# r0_2_6.net
KiCad netlist of a schematic drawn in EAGLE
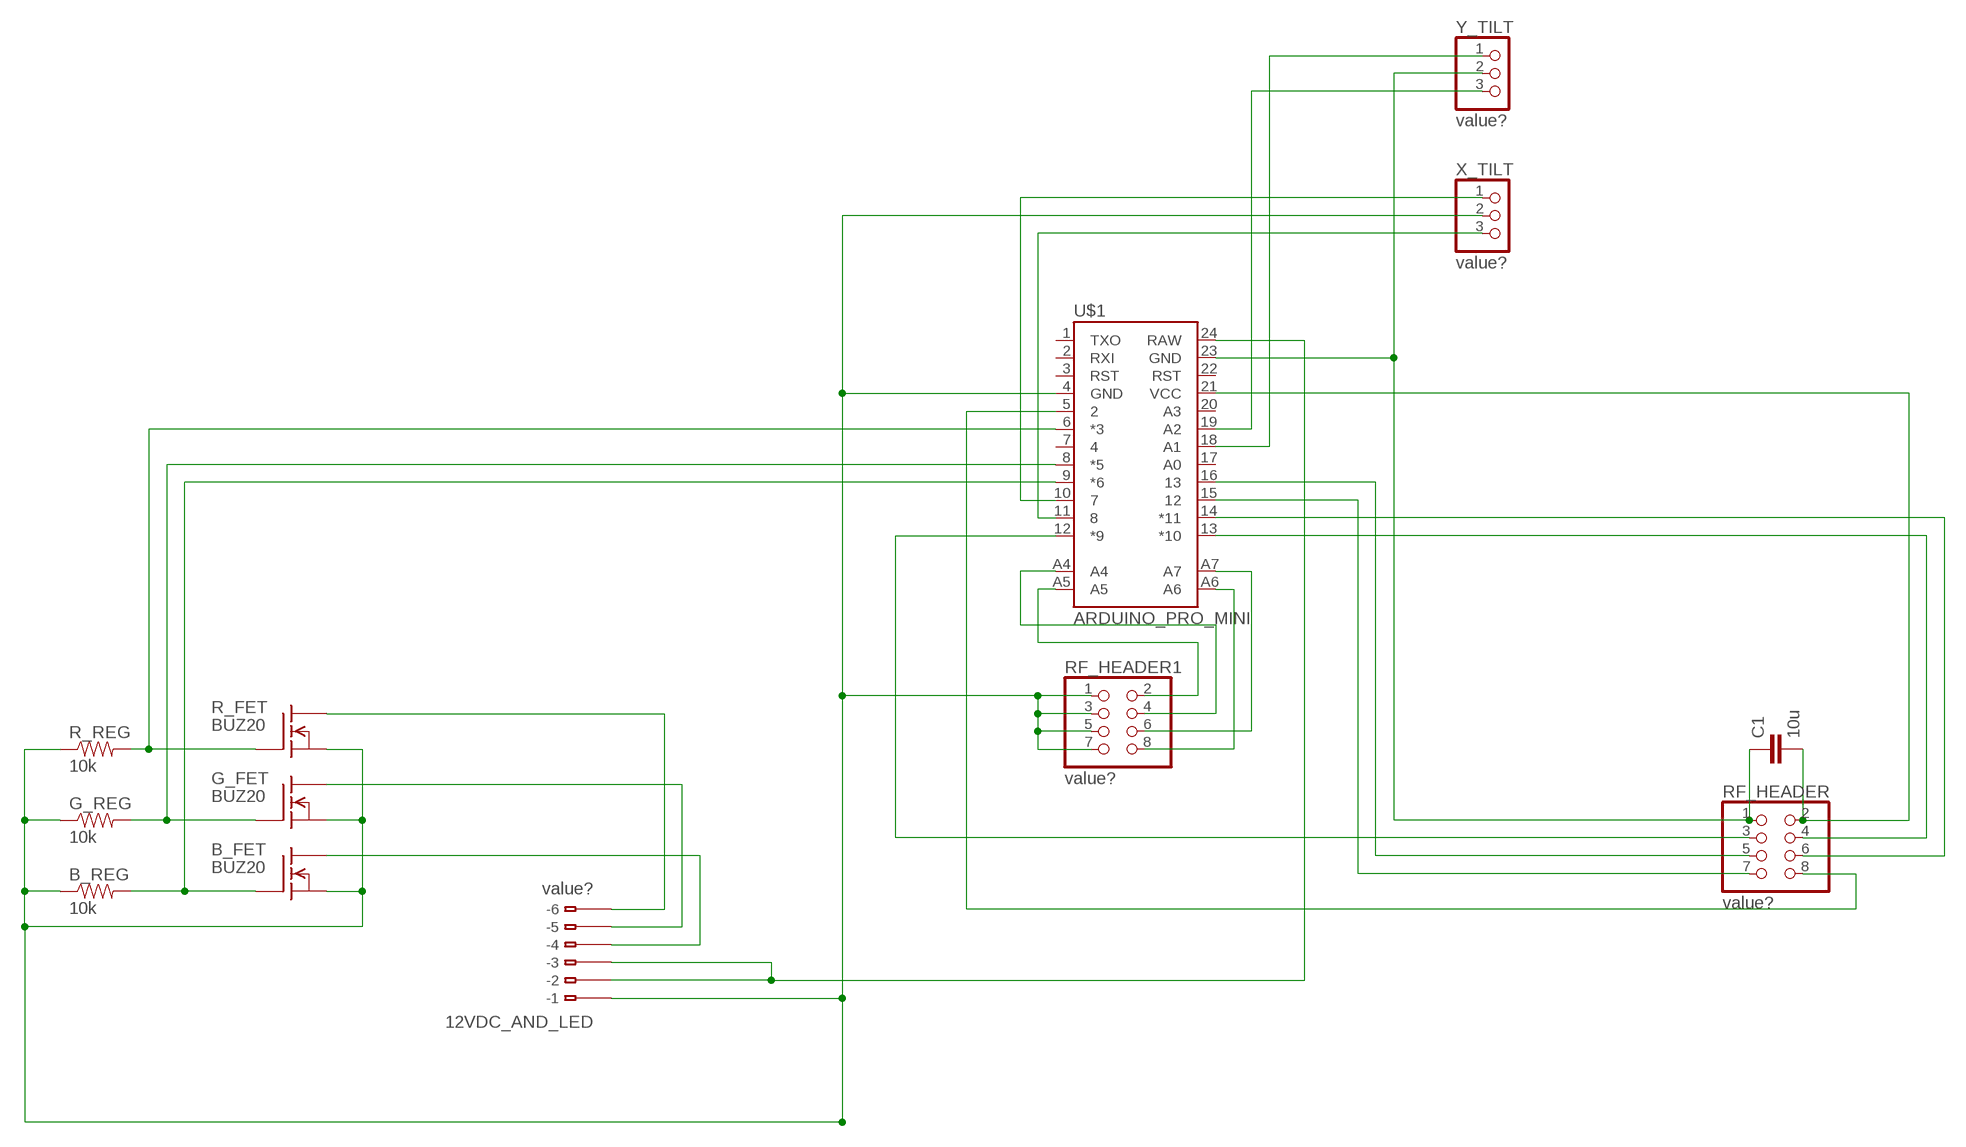
[diagram p0: schematic, sheet 1]

(export (version "E")
  (design (tool "Eeschema 10.0.6"))
  (components
    (comp (ref "12VDC_AND_LED")
      (value "value?")
      (footprint "eagle-import:234-206")
      (fields (field (name "MPN") "234-206"))
      (libsource (lib "eagle-import") (part "234-206"))
    )
    (comp (ref "B_FET")
      (value "BUZ20")
      (footprint "eagle-import:TO220")
      (libsource (lib "eagle-import") (part "BUZ20"))
    )
    (comp (ref "B_REG")
      (value "10k")
      (footprint "eagle-import:AXIAL-0.4")
      (libsource (lib "eagle-import") (part "RESISTORPTH-1/4W"))
    )
    (comp (ref "C1")
      (value "10u")
      (footprint "eagle-import:CAP-PTH-SMALL")
      (libsource (lib "eagle-import") (part "CAPPTH"))
    )
    (comp (ref "G_FET")
      (value "BUZ20")
      (footprint "eagle-import:TO220")
      (libsource (lib "eagle-import") (part "BUZ20"))
    )
    (comp (ref "G_REG")
      (value "10k")
      (footprint "eagle-import:AXIAL-0.4")
      (libsource (lib "eagle-import") (part "RESISTORPTH-1/4W"))
    )
    (comp (ref "RF_HEADER")
      (value "value?")
      (footprint "eagle-import:2X04")
      (libsource (lib "eagle-import") (part "PINHD-2X4"))
    )
    (comp (ref "RF_HEADER1")
      (value "value?")
      (footprint "eagle-import:2X04")
      (libsource (lib "eagle-import") (part "PINHD-2X4"))
    )
    (comp (ref "R_FET")
      (value "BUZ20")
      (footprint "eagle-import:TO220")
      (libsource (lib "eagle-import") (part "BUZ20"))
    )
    (comp (ref "R_REG")
      (value "10k")
      (footprint "eagle-import:AXIAL-0.4")
      (libsource (lib "eagle-import") (part "RESISTORPTH-1/4W"))
    )
    (comp (ref "U$1")
      (value "ARDUINO_PRO_MINI")
      (footprint "eagle-import:ARDUINO_PRO_MINI")
      (libsource (lib "eagle-import") (part "ARDUINO_PRO_MINI"))
    )
    (comp (ref "X_TILT")
      (value "value?")
      (footprint "eagle-import:1X03")
      (libsource (lib "eagle-import") (part "PINHD-1X3"))
    )
    (comp (ref "Y_TILT")
      (value "value?")
      (footprint "eagle-import:1X03")
      (libsource (lib "eagle-import") (part "PINHD-1X3"))
    )
  )
  (nets
    (net (code "1") (name "Net-(12VDC_AND_LED-B-1)") (class "Default")
      (node (ref "12VDC_AND_LED") (pin "B1") (pinfunction "B-1_B1") (pintype "passive"))
      (node (ref "B_FET") (pin "3") (pinfunction "S_3") (pintype "passive"))
      (node (ref "B_REG") (pin "P$1") (pinfunction "1_P$1") (pintype "passive"))
      (node (ref "G_FET") (pin "3") (pinfunction "S_3") (pintype "passive"))
      (node (ref "G_REG") (pin "P$1") (pinfunction "1_P$1") (pintype "passive"))
      (node (ref "RF_HEADER1") (pin "1") (pinfunction "1_1") (pintype "passive"))
      (node (ref "RF_HEADER1") (pin "3") (pinfunction "3_3") (pintype "passive"))
      (node (ref "RF_HEADER1") (pin "5") (pinfunction "5_5") (pintype "passive"))
      (node (ref "RF_HEADER1") (pin "7") (pinfunction "7_7") (pintype "passive"))
      (node (ref "R_FET") (pin "3") (pinfunction "S_3") (pintype "passive"))
      (node (ref "R_REG") (pin "P$1") (pinfunction "1_P$1") (pintype "passive"))
      (node (ref "U$1") (pin "4") (pinfunction "GND_4") (pintype "bidirectional"))
      (node (ref "X_TILT") (pin "2") (pinfunction "2_2") (pintype "passive"))
    )
    (net (code "2") (name "Net-(12VDC_AND_LED-B-2)") (class "Default")
      (node (ref "12VDC_AND_LED") (pin "B2") (pinfunction "B-2_B2") (pintype "passive"))
      (node (ref "12VDC_AND_LED") (pin "B3") (pinfunction "B-3_B3") (pintype "passive"))
      (node (ref "U$1") (pin "24") (pinfunction "RAW_24") (pintype "bidirectional"))
    )
    (net (code "3") (name "Net-(12VDC_AND_LED-B-4)") (class "Default")
      (node (ref "12VDC_AND_LED") (pin "B4") (pinfunction "B-4_B4") (pintype "passive"))
      (node (ref "B_FET") (pin "2") (pinfunction "D_2") (pintype "passive"))
    )
    (net (code "4") (name "Net-(12VDC_AND_LED-B-5)") (class "Default")
      (node (ref "12VDC_AND_LED") (pin "B5") (pinfunction "B-5_B5") (pintype "passive"))
      (node (ref "G_FET") (pin "2") (pinfunction "D_2") (pintype "passive"))
    )
    (net (code "5") (name "Net-(12VDC_AND_LED-B-6)") (class "Default")
      (node (ref "12VDC_AND_LED") (pin "B6") (pinfunction "B-6_B6") (pintype "passive"))
      (node (ref "R_FET") (pin "2") (pinfunction "D_2") (pintype "passive"))
    )
    (net (code "6") (name "Net-(B_FET-G)") (class "Default")
      (node (ref "B_FET") (pin "1") (pinfunction "G_1") (pintype "passive"))
      (node (ref "B_REG") (pin "P$2") (pinfunction "2_P$2") (pintype "passive"))
      (node (ref "U$1") (pin "9") (pinfunction "*6_9") (pintype "bidirectional"))
    )
    (net (code "7") (name "Net-(C1-Pad1)") (class "Default")
      (node (ref "C1") (pin "1") (pinfunction "1_1") (pintype "passive"))
      (node (ref "RF_HEADER") (pin "1") (pinfunction "1_1") (pintype "passive"))
      (node (ref "U$1") (pin "23") (pinfunction "GND_23") (pintype "bidirectional"))
      (node (ref "Y_TILT") (pin "2") (pinfunction "2_2") (pintype "passive"))
    )
    (net (code "8") (name "Net-(G_FET-G)") (class "Default")
      (node (ref "G_FET") (pin "1") (pinfunction "G_1") (pintype "passive"))
      (node (ref "G_REG") (pin "P$2") (pinfunction "2_P$2") (pintype "passive"))
      (node (ref "U$1") (pin "8") (pinfunction "*5_8") (pintype "bidirectional"))
    )
    (net (code "9") (name "Net-(RF_HEADER1-Pad2)") (class "Default")
      (node (ref "RF_HEADER1") (pin "2") (pinfunction "2_2") (pintype "passive"))
      (node (ref "U$1") (pin "A5") (pinfunction "A5_A5") (pintype "bidirectional"))
    )
    (net (code "10") (name "Net-(RF_HEADER1-Pad4)") (class "Default")
      (node (ref "RF_HEADER1") (pin "4") (pinfunction "4_4") (pintype "passive"))
      (node (ref "U$1") (pin "A4") (pinfunction "A4_A4") (pintype "bidirectional"))
    )
    (net (code "11") (name "Net-(RF_HEADER1-Pad6)") (class "Default")
      (node (ref "RF_HEADER1") (pin "6") (pinfunction "6_6") (pintype "passive"))
      (node (ref "U$1") (pin "A7") (pinfunction "A7_A7") (pintype "bidirectional"))
    )
    (net (code "12") (name "Net-(RF_HEADER1-Pad8)") (class "Default")
      (node (ref "RF_HEADER1") (pin "8") (pinfunction "8_8") (pintype "passive"))
      (node (ref "U$1") (pin "A6") (pinfunction "A6_A6") (pintype "bidirectional"))
    )
    (net (code "13") (name "Net-(R_FET-G)") (class "Default")
      (node (ref "R_FET") (pin "1") (pinfunction "G_1") (pintype "passive"))
      (node (ref "R_REG") (pin "P$2") (pinfunction "2_P$2") (pintype "passive"))
      (node (ref "U$1") (pin "6") (pinfunction "*3_6") (pintype "bidirectional"))
    )
    (net (code "14") (name "Net-(U$1-*9)") (class "Default")
      (node (ref "RF_HEADER") (pin "3") (pinfunction "3_3") (pintype "passive"))
      (node (ref "U$1") (pin "12") (pinfunction "*9_12") (pintype "bidirectional"))
    )
    (net (code "15") (name "Net-(U$1-*10)") (class "Default")
      (node (ref "RF_HEADER") (pin "4") (pinfunction "4_4") (pintype "passive"))
      (node (ref "U$1") (pin "13") (pinfunction "*10_13") (pintype "bidirectional"))
    )
    (net (code "16") (name "Net-(U$1-*11)") (class "Default")
      (node (ref "RF_HEADER") (pin "6") (pinfunction "6_6") (pintype "passive"))
      (node (ref "U$1") (pin "14") (pinfunction "*11_14") (pintype "bidirectional"))
    )
    (net (code "17") (name "Net-(U$1-2)") (class "Default")
      (node (ref "RF_HEADER") (pin "8") (pinfunction "8_8") (pintype "passive"))
      (node (ref "U$1") (pin "5") (pinfunction "2_5") (pintype "bidirectional"))
    )
    (net (code "18") (name "Net-(U$1-7)") (class "Default")
      (node (ref "U$1") (pin "10") (pinfunction "7_10") (pintype "bidirectional"))
      (node (ref "X_TILT") (pin "1") (pinfunction "1_1") (pintype "passive"))
    )
    (net (code "19") (name "Net-(U$1-8)") (class "Default")
      (node (ref "U$1") (pin "11") (pinfunction "8_11") (pintype "bidirectional"))
      (node (ref "X_TILT") (pin "3") (pinfunction "3_3") (pintype "passive"))
    )
    (net (code "20") (name "Net-(U$1-12)") (class "Default")
      (node (ref "RF_HEADER") (pin "7") (pinfunction "7_7") (pintype "passive"))
      (node (ref "U$1") (pin "15") (pinfunction "12_15") (pintype "bidirectional"))
    )
    (net (code "21") (name "Net-(U$1-13)") (class "Default")
      (node (ref "RF_HEADER") (pin "5") (pinfunction "5_5") (pintype "passive"))
      (node (ref "U$1") (pin "16") (pinfunction "13_16") (pintype "bidirectional"))
    )
    (net (code "22") (name "Net-(U$1-A1)") (class "Default")
      (node (ref "U$1") (pin "18") (pinfunction "A1_18") (pintype "bidirectional"))
      (node (ref "Y_TILT") (pin "1") (pinfunction "1_1") (pintype "passive"))
    )
    (net (code "23") (name "Net-(U$1-A2)") (class "Default")
      (node (ref "U$1") (pin "19") (pinfunction "A2_19") (pintype "bidirectional"))
      (node (ref "Y_TILT") (pin "3") (pinfunction "3_3") (pintype "passive"))
    )
    (net (code "24") (name "Net-(U$1-VCC)") (class "Default")
      (node (ref "C1") (pin "2") (pinfunction "2_2") (pintype "passive"))
      (node (ref "RF_HEADER") (pin "2") (pinfunction "2_2") (pintype "passive"))
      (node (ref "U$1") (pin "21") (pinfunction "VCC_21") (pintype "bidirectional"))
    )
    (net (code "25") (name "unconnected-(12VDC_AND_LED--1-PadA1)") (class "Default")
      (node (ref "12VDC_AND_LED") (pin "A1") (pinfunction "-1_A1") (pintype "passive"))
    )
    (net (code "26") (name "unconnected-(12VDC_AND_LED--2-PadA2)") (class "Default")
      (node (ref "12VDC_AND_LED") (pin "A2") (pinfunction "-2_A2") (pintype "passive"))
    )
    (net (code "27") (name "unconnected-(12VDC_AND_LED--3-PadA3)") (class "Default")
      (node (ref "12VDC_AND_LED") (pin "A3") (pinfunction "-3_A3") (pintype "passive"))
    )
    (net (code "28") (name "unconnected-(12VDC_AND_LED--4-PadA4)") (class "Default")
      (node (ref "12VDC_AND_LED") (pin "A4") (pinfunction "-4_A4") (pintype "passive"))
    )
    (net (code "29") (name "unconnected-(12VDC_AND_LED--5-PadA5)") (class "Default")
      (node (ref "12VDC_AND_LED") (pin "A5") (pinfunction "-5_A5") (pintype "passive"))
    )
    (net (code "30") (name "unconnected-(12VDC_AND_LED--6-PadA6)") (class "Default")
      (node (ref "12VDC_AND_LED") (pin "A6") (pinfunction "-6_A6") (pintype "passive"))
    )
    (net (code "31") (name "unconnected-(U$1-4-Pad7)") (class "Default")
      (node (ref "U$1") (pin "7") (pinfunction "4_7") (pintype "bidirectional"))
    )
    (net (code "32") (name "unconnected-(U$1-A0-Pad17)") (class "Default")
      (node (ref "U$1") (pin "17") (pinfunction "A0_17") (pintype "bidirectional"))
    )
    (net (code "33") (name "unconnected-(U$1-A3-Pad20)") (class "Default")
      (node (ref "U$1") (pin "20") (pinfunction "A3_20") (pintype "bidirectional"))
    )
    (net (code "34") (name "unconnected-(U$1-RST-Pad3)") (class "Default")
      (node (ref "U$1") (pin "3") (pinfunction "RST_3") (pintype "bidirectional"))
    )
    (net (code "35") (name "unconnected-(U$1-RST-Pad22)") (class "Default")
      (node (ref "U$1") (pin "22") (pinfunction "RST_22") (pintype "bidirectional"))
    )
    (net (code "36") (name "unconnected-(U$1-RXI-Pad2)") (class "Default")
      (node (ref "U$1") (pin "2") (pinfunction "RXI_2") (pintype "bidirectional"))
    )
    (net (code "37") (name "unconnected-(U$1-TXO-Pad1)") (class "Default")
      (node (ref "U$1") (pin "1") (pinfunction "TXO_1") (pintype "bidirectional"))
    )
  )
)
